# HOMADOS_v1.net
KiCad netlist of a schematic drawn in EAGLE
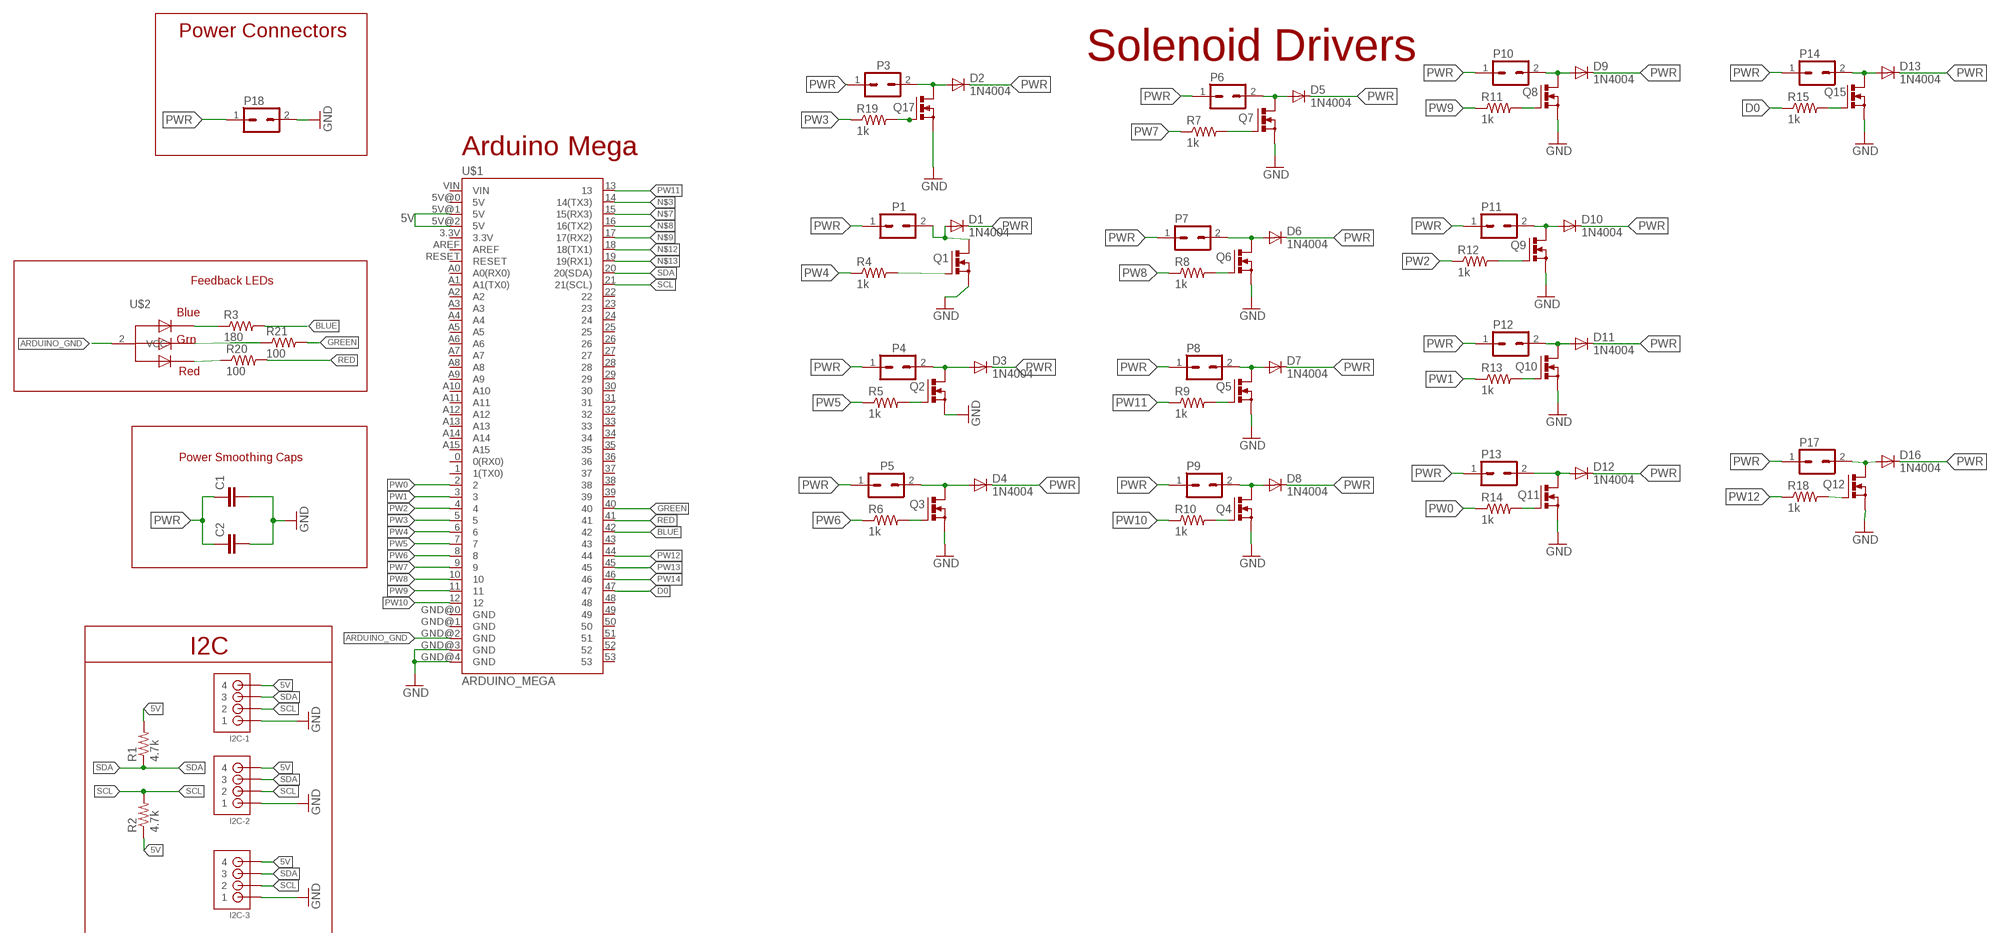
[diagram p0: schematic, sheet 1]

(export (version "E")
  (design (tool "Eeschema 10.0.6"))
  (components
    (comp (ref "C1")
      (value "CAPPTH1")
      (footprint "eagle-import:CAP-PTH-5MM")
      (libsource (lib "eagle-import") (part "CAPPTH1"))
    )
    (comp (ref "C2")
      (value "CAPPTH3")
      (footprint "eagle-import:CAP-PTH-LARGE")
      (libsource (lib "eagle-import") (part "CAPPTH3"))
    )
    (comp (ref "D1")
      (value "1N4004")
      (footprint "eagle-import:DO41-10")
      (libsource (lib "eagle-import") (part "1N4004"))
    )
    (comp (ref "D2")
      (value "1N4004")
      (footprint "eagle-import:DO41-10")
      (libsource (lib "eagle-import") (part "1N4004"))
    )
    (comp (ref "D3")
      (value "1N4004")
      (footprint "eagle-import:DO41-10")
      (libsource (lib "eagle-import") (part "1N4004"))
    )
    (comp (ref "D4")
      (value "1N4004")
      (footprint "eagle-import:DO41-10")
      (libsource (lib "eagle-import") (part "1N4004"))
    )
    (comp (ref "D5")
      (value "1N4004")
      (footprint "eagle-import:DO41-10")
      (libsource (lib "eagle-import") (part "1N4004"))
    )
    (comp (ref "D6")
      (value "1N4004")
      (footprint "eagle-import:DO41-10")
      (libsource (lib "eagle-import") (part "1N4004"))
    )
    (comp (ref "D7")
      (value "1N4004")
      (footprint "eagle-import:DO41-10")
      (libsource (lib "eagle-import") (part "1N4004"))
    )
    (comp (ref "D8")
      (value "1N4004")
      (footprint "eagle-import:DO41-10")
      (libsource (lib "eagle-import") (part "1N4004"))
    )
    (comp (ref "D9")
      (value "1N4004")
      (footprint "eagle-import:DO41-10")
      (libsource (lib "eagle-import") (part "1N4004"))
    )
    (comp (ref "D10")
      (value "1N4004")
      (footprint "eagle-import:DO41-10")
      (libsource (lib "eagle-import") (part "1N4004"))
    )
    (comp (ref "D11")
      (value "1N4004")
      (footprint "eagle-import:DO41-10")
      (libsource (lib "eagle-import") (part "1N4004"))
    )
    (comp (ref "D12")
      (value "1N4004")
      (footprint "eagle-import:DO41-10")
      (libsource (lib "eagle-import") (part "1N4004"))
    )
    (comp (ref "D13")
      (value "1N4004")
      (footprint "eagle-import:DO41-10")
      (libsource (lib "eagle-import") (part "1N4004"))
    )
    (comp (ref "D16")
      (value "1N4004")
      (footprint "eagle-import:DO41-10")
      (libsource (lib "eagle-import") (part "1N4004"))
    )
    (comp (ref "I2C-1")
      (value "JST-PH_4-PIN_HEADER")
      (footprint "eagle-import:JST_B4B-PH_HEADER")
      (libsource (lib "eagle-import") (part "JST-PH_4-PIN_HEADER"))
    )
    (comp (ref "I2C-2")
      (value "JST-PH_4-PIN_HEADER")
      (footprint "eagle-import:JST_B4B-PH_HEADER")
      (libsource (lib "eagle-import") (part "JST-PH_4-PIN_HEADER"))
    )
    (comp (ref "I2C-3")
      (value "JST-PH_4-PIN_HEADER")
      (footprint "eagle-import:JST_B4B-PH_HEADER")
      (libsource (lib "eagle-import") (part "JST-PH_4-PIN_HEADER"))
    )
    (comp (ref "P1")
      (value "39-30-02")
      (footprint "eagle-import:39-30-_02_")
      (libsource (lib "eagle-import") (part "39-30-?02?"))
    )
    (comp (ref "P3")
      (value "39-30-02")
      (footprint "eagle-import:39-30-_02_")
      (libsource (lib "eagle-import") (part "39-30-?02?"))
    )
    (comp (ref "P4")
      (value "39-30-02")
      (footprint "eagle-import:39-30-_02_")
      (libsource (lib "eagle-import") (part "39-30-?02?"))
    )
    (comp (ref "P5")
      (value "39-30-02")
      (footprint "eagle-import:39-30-_02_")
      (libsource (lib "eagle-import") (part "39-30-?02?"))
    )
    (comp (ref "P6")
      (value "39-30-02")
      (footprint "eagle-import:39-30-_02_")
      (libsource (lib "eagle-import") (part "39-30-?02?"))
    )
    (comp (ref "P7")
      (value "39-30-02")
      (footprint "eagle-import:39-30-_02_")
      (libsource (lib "eagle-import") (part "39-30-?02?"))
    )
    (comp (ref "P8")
      (value "39-30-02")
      (footprint "eagle-import:39-30-_02_")
      (libsource (lib "eagle-import") (part "39-30-?02?"))
    )
    (comp (ref "P9")
      (value "39-30-02")
      (footprint "eagle-import:39-30-_02_")
      (libsource (lib "eagle-import") (part "39-30-?02?"))
    )
    (comp (ref "P10")
      (value "39-30-02")
      (footprint "eagle-import:39-30-_02_")
      (libsource (lib "eagle-import") (part "39-30-?02?"))
    )
    (comp (ref "P11")
      (value "39-30-02")
      (footprint "eagle-import:39-30-_02_")
      (libsource (lib "eagle-import") (part "39-30-?02?"))
    )
    (comp (ref "P12")
      (value "39-30-02")
      (footprint "eagle-import:39-30-_02_")
      (libsource (lib "eagle-import") (part "39-30-?02?"))
    )
    (comp (ref "P13")
      (value "39-30-02")
      (footprint "eagle-import:39-30-_02_")
      (libsource (lib "eagle-import") (part "39-30-?02?"))
    )
    (comp (ref "P14")
      (value "39-30-02")
      (footprint "eagle-import:39-30-_02_")
      (libsource (lib "eagle-import") (part "39-30-?02?"))
    )
    (comp (ref "P17")
      (value "39-30-02")
      (footprint "eagle-import:39-30-_02_")
      (libsource (lib "eagle-import") (part "39-30-?02?"))
    )
    (comp (ref "P18")
      (value "39-30-02")
      (footprint "eagle-import:39-30-_02_")
      (libsource (lib "eagle-import") (part "39-30-?02?"))
    )
    (comp (ref "Q1")
      (value "PMOSFET_NTO220BV")
      (footprint "eagle-import:TO220BV")
      (libsource (lib "eagle-import") (part "PMOSFET_NTO220BV"))
    )
    (comp (ref "Q2")
      (value "PMOSFET_NTO220BV")
      (footprint "eagle-import:TO220BV")
      (libsource (lib "eagle-import") (part "PMOSFET_NTO220BV"))
    )
    (comp (ref "Q3")
      (value "PMOSFET_NTO220BV")
      (footprint "eagle-import:TO220BV")
      (libsource (lib "eagle-import") (part "PMOSFET_NTO220BV"))
    )
    (comp (ref "Q4")
      (value "PMOSFET_NTO220BV")
      (footprint "eagle-import:TO220BV")
      (libsource (lib "eagle-import") (part "PMOSFET_NTO220BV"))
    )
    (comp (ref "Q5")
      (value "PMOSFET_NTO220BV")
      (footprint "eagle-import:TO220BV")
      (libsource (lib "eagle-import") (part "PMOSFET_NTO220BV"))
    )
    (comp (ref "Q6")
      (value "PMOSFET_NTO220BV")
      (footprint "eagle-import:TO220BV")
      (libsource (lib "eagle-import") (part "PMOSFET_NTO220BV"))
    )
    (comp (ref "Q7")
      (value "PMOSFET_NTO220BV")
      (footprint "eagle-import:TO220BV")
      (libsource (lib "eagle-import") (part "PMOSFET_NTO220BV"))
    )
    (comp (ref "Q8")
      (value "PMOSFET_NTO220BV")
      (footprint "eagle-import:TO220BV")
      (libsource (lib "eagle-import") (part "PMOSFET_NTO220BV"))
    )
    (comp (ref "Q9")
      (value "PMOSFET_NTO220BV")
      (footprint "eagle-import:TO220BV")
      (libsource (lib "eagle-import") (part "PMOSFET_NTO220BV"))
    )
    (comp (ref "Q10")
      (value "PMOSFET_NTO220BV")
      (footprint "eagle-import:TO220BV")
      (libsource (lib "eagle-import") (part "PMOSFET_NTO220BV"))
    )
    (comp (ref "Q11")
      (value "PMOSFET_NTO220BV")
      (footprint "eagle-import:TO220BV")
      (libsource (lib "eagle-import") (part "PMOSFET_NTO220BV"))
    )
    (comp (ref "Q12")
      (value "PMOSFET_NTO220BV")
      (footprint "eagle-import:TO220BV")
      (libsource (lib "eagle-import") (part "PMOSFET_NTO220BV"))
    )
    (comp (ref "Q15")
      (value "PMOSFET_NTO220BV")
      (footprint "eagle-import:TO220BV")
      (libsource (lib "eagle-import") (part "PMOSFET_NTO220BV"))
    )
    (comp (ref "Q17")
      (value "PMOSFET_NTO220BV")
      (footprint "eagle-import:TO220BV")
      (libsource (lib "eagle-import") (part "PMOSFET_NTO220BV"))
    )
    (comp (ref "R1")
      (value "4.7k")
      (footprint "eagle-import:AXIAL-0.3-KIT")
      (libsource (lib "eagle-import") (part "RESISTORKIT"))
    )
    (comp (ref "R2")
      (value "4.7k")
      (footprint "eagle-import:AXIAL-0.3-KIT")
      (libsource (lib "eagle-import") (part "RESISTORKIT"))
    )
    (comp (ref "R3")
      (value "180")
      (footprint "eagle-import:AXIAL-0.3-KIT")
      (libsource (lib "eagle-import") (part "RESISTORKIT"))
    )
    (comp (ref "R4")
      (value "1k")
      (footprint "eagle-import:AXIAL-0.3-KIT")
      (libsource (lib "eagle-import") (part "RESISTORKIT"))
    )
    (comp (ref "R5")
      (value "1k")
      (footprint "eagle-import:AXIAL-0.3-KIT")
      (libsource (lib "eagle-import") (part "RESISTORKIT"))
    )
    (comp (ref "R6")
      (value "1k")
      (footprint "eagle-import:AXIAL-0.3-KIT")
      (libsource (lib "eagle-import") (part "RESISTORKIT"))
    )
    (comp (ref "R7")
      (value "1k")
      (footprint "eagle-import:AXIAL-0.3-KIT")
      (libsource (lib "eagle-import") (part "RESISTORKIT"))
    )
    (comp (ref "R8")
      (value "1k")
      (footprint "eagle-import:AXIAL-0.3-KIT")
      (libsource (lib "eagle-import") (part "RESISTORKIT"))
    )
    (comp (ref "R9")
      (value "1k")
      (footprint "eagle-import:AXIAL-0.3-KIT")
      (libsource (lib "eagle-import") (part "RESISTORKIT"))
    )
    (comp (ref "R10")
      (value "1k")
      (footprint "eagle-import:AXIAL-0.3-KIT")
      (libsource (lib "eagle-import") (part "RESISTORKIT"))
    )
    (comp (ref "R11")
      (value "1k")
      (footprint "eagle-import:AXIAL-0.3-KIT")
      (libsource (lib "eagle-import") (part "RESISTORKIT"))
    )
    (comp (ref "R12")
      (value "1k")
      (footprint "eagle-import:AXIAL-0.3-KIT")
      (libsource (lib "eagle-import") (part "RESISTORKIT"))
    )
    (comp (ref "R13")
      (value "1k")
      (footprint "eagle-import:AXIAL-0.3-KIT")
      (libsource (lib "eagle-import") (part "RESISTORKIT"))
    )
    (comp (ref "R14")
      (value "1k")
      (footprint "eagle-import:AXIAL-0.3-KIT")
      (libsource (lib "eagle-import") (part "RESISTORKIT"))
    )
    (comp (ref "R15")
      (value "1k")
      (footprint "eagle-import:AXIAL-0.3-KIT")
      (libsource (lib "eagle-import") (part "RESISTORKIT"))
    )
    (comp (ref "R18")
      (value "1k")
      (footprint "eagle-import:AXIAL-0.3-KIT")
      (libsource (lib "eagle-import") (part "RESISTORKIT"))
    )
    (comp (ref "R19")
      (value "1k")
      (footprint "eagle-import:AXIAL-0.3-KIT")
      (libsource (lib "eagle-import") (part "RESISTORKIT"))
    )
    (comp (ref "R20")
      (value "100")
      (footprint "eagle-import:AXIAL-0.3-KIT")
      (libsource (lib "eagle-import") (part "RESISTORKIT"))
    )
    (comp (ref "R21")
      (value "100")
      (footprint "eagle-import:AXIAL-0.3-KIT")
      (libsource (lib "eagle-import") (part "RESISTORKIT"))
    )
    (comp (ref "U$1")
      (value "ARDUINO_MEGA")
      (footprint "eagle-import:ARDUINO_MEGA")
      (libsource (lib "eagle-import") (part "ARDUINO_MEGA"))
    )
    (comp (ref "U$2")
      (value "RGBLED_CA")
      (footprint "eagle-import:LED5MMRGB")
      (libsource (lib "eagle-import") (part "RGBLED_CA"))
    )
  )
  (nets
    (net (code "1") (name "5V") (class "Default")
      (node (ref "I2C-1") (pin "P4") (pinfunction "4_P4") (pintype "bidirectional"))
      (node (ref "I2C-2") (pin "P4") (pinfunction "4_P4") (pintype "bidirectional"))
      (node (ref "I2C-3") (pin "P4") (pinfunction "4_P4") (pintype "bidirectional"))
      (node (ref "R1") (pin "P$2") (pinfunction "2_P$2") (pintype "passive"))
      (node (ref "R2") (pin "P$1") (pinfunction "1_P$1") (pintype "passive"))
      (node (ref "U$1") (pin "5V@1") (pinfunction "5V_5V@1") (pintype "bidirectional"))
      (node (ref "U$1") (pin "5V@2") (pinfunction "5V_5V@2") (pintype "bidirectional"))
    )
    (net (code "2") (name "ARDUINO_GND") (class "Default")
      (node (ref "U$1") (pin "GND@2") (pinfunction "GND_GND@2") (pintype "bidirectional"))
      (node (ref "U$2") (pin "2") (pinfunction "VCC_2") (pintype "bidirectional"))
    )
    (net (code "3") (name "BLUE") (class "Default")
      (node (ref "R3") (pin "P$2") (pinfunction "2_P$2") (pintype "passive"))
      (node (ref "U$1") (pin "42") (pinfunction "42_42") (pintype "bidirectional"))
    )
    (net (code "4") (name "D0") (class "Default")
      (node (ref "R15") (pin "P$1") (pinfunction "1_P$1") (pintype "passive"))
      (node (ref "U$1") (pin "47") (pinfunction "47_47") (pintype "bidirectional"))
    )
    (net (code "5") (name "GND") (class "Default")
      (node (ref "C1") (pin "2") (pinfunction "2_2") (pintype "passive"))
      (node (ref "C2") (pin "2") (pinfunction "2_2") (pintype "passive"))
      (node (ref "I2C-1") (pin "P1") (pinfunction "1_P1") (pintype "bidirectional"))
      (node (ref "I2C-2") (pin "P1") (pinfunction "1_P1") (pintype "bidirectional"))
      (node (ref "I2C-3") (pin "P1") (pinfunction "1_P1") (pintype "bidirectional"))
      (node (ref "P18") (pin "2") (pinfunction "2_2") (pintype "passive"))
      (node (ref "Q1") (pin "S") (pinfunction "S_S") (pintype "passive"))
      (node (ref "Q10") (pin "S") (pinfunction "S_S") (pintype "passive"))
      (node (ref "Q11") (pin "S") (pinfunction "S_S") (pintype "passive"))
      (node (ref "Q12") (pin "S") (pinfunction "S_S") (pintype "passive"))
      (node (ref "Q15") (pin "S") (pinfunction "S_S") (pintype "passive"))
      (node (ref "Q17") (pin "S") (pinfunction "S_S") (pintype "passive"))
      (node (ref "Q2") (pin "S") (pinfunction "S_S") (pintype "passive"))
      (node (ref "Q3") (pin "S") (pinfunction "S_S") (pintype "passive"))
      (node (ref "Q4") (pin "S") (pinfunction "S_S") (pintype "passive"))
      (node (ref "Q5") (pin "S") (pinfunction "S_S") (pintype "passive"))
      (node (ref "Q6") (pin "S") (pinfunction "S_S") (pintype "passive"))
      (node (ref "Q7") (pin "S") (pinfunction "S_S") (pintype "passive"))
      (node (ref "Q8") (pin "S") (pinfunction "S_S") (pintype "passive"))
      (node (ref "Q9") (pin "S") (pinfunction "S_S") (pintype "passive"))
      (node (ref "U$1") (pin "GND@3") (pinfunction "GND_GND@3") (pintype "bidirectional"))
      (node (ref "U$1") (pin "GND@4") (pinfunction "GND_GND@4") (pintype "bidirectional"))
    )
    (net (code "6") (name "GREEN") (class "Default")
      (node (ref "R21") (pin "P$2") (pinfunction "2_P$2") (pintype "passive"))
      (node (ref "U$1") (pin "40") (pinfunction "40_40") (pintype "bidirectional"))
    )
    (net (code "7") (name "N$3") (class "Default")
      (node (ref "U$1") (pin "14") (pinfunction "14(TX3)_14") (pintype "bidirectional"))
    )
    (net (code "8") (name "N$7") (class "Default")
      (node (ref "U$1") (pin "15") (pinfunction "15(RX3)_15") (pintype "bidirectional"))
    )
    (net (code "9") (name "N$8") (class "Default")
      (node (ref "U$1") (pin "16") (pinfunction "16(TX2)_16") (pintype "bidirectional"))
    )
    (net (code "10") (name "N$9") (class "Default")
      (node (ref "U$1") (pin "17") (pinfunction "17(RX2)_17") (pintype "bidirectional"))
    )
    (net (code "11") (name "N$12") (class "Default")
      (node (ref "U$1") (pin "18") (pinfunction "18(TX1)_18") (pintype "bidirectional"))
    )
    (net (code "12") (name "N$13") (class "Default")
      (node (ref "U$1") (pin "19") (pinfunction "19(RX1)_19") (pintype "bidirectional"))
    )
    (net (code "13") (name "Net-(D1-PadA)") (class "Default")
      (node (ref "D1") (pin "A") (pinfunction "A_A") (pintype "passive"))
      (node (ref "P1") (pin "2") (pinfunction "2_2") (pintype "passive"))
      (node (ref "Q1") (pin "D") (pinfunction "D_D") (pintype "passive"))
    )
    (net (code "14") (name "Net-(D2-PadA)") (class "Default")
      (node (ref "D2") (pin "A") (pinfunction "A_A") (pintype "passive"))
      (node (ref "P3") (pin "2") (pinfunction "2_2") (pintype "passive"))
      (node (ref "Q17") (pin "D") (pinfunction "D_D") (pintype "passive"))
    )
    (net (code "15") (name "Net-(D3-PadA)") (class "Default")
      (node (ref "D3") (pin "A") (pinfunction "A_A") (pintype "passive"))
      (node (ref "P4") (pin "2") (pinfunction "2_2") (pintype "passive"))
      (node (ref "Q2") (pin "D") (pinfunction "D_D") (pintype "passive"))
    )
    (net (code "16") (name "Net-(D4-PadA)") (class "Default")
      (node (ref "D4") (pin "A") (pinfunction "A_A") (pintype "passive"))
      (node (ref "P5") (pin "2") (pinfunction "2_2") (pintype "passive"))
      (node (ref "Q3") (pin "D") (pinfunction "D_D") (pintype "passive"))
    )
    (net (code "17") (name "Net-(D5-PadA)") (class "Default")
      (node (ref "D5") (pin "A") (pinfunction "A_A") (pintype "passive"))
      (node (ref "P6") (pin "2") (pinfunction "2_2") (pintype "passive"))
      (node (ref "Q7") (pin "D") (pinfunction "D_D") (pintype "passive"))
    )
    (net (code "18") (name "Net-(D6-PadA)") (class "Default")
      (node (ref "D6") (pin "A") (pinfunction "A_A") (pintype "passive"))
      (node (ref "P7") (pin "2") (pinfunction "2_2") (pintype "passive"))
      (node (ref "Q6") (pin "D") (pinfunction "D_D") (pintype "passive"))
    )
    (net (code "19") (name "Net-(D7-PadA)") (class "Default")
      (node (ref "D7") (pin "A") (pinfunction "A_A") (pintype "passive"))
      (node (ref "P8") (pin "2") (pinfunction "2_2") (pintype "passive"))
      (node (ref "Q5") (pin "D") (pinfunction "D_D") (pintype "passive"))
    )
    (net (code "20") (name "Net-(D8-PadA)") (class "Default")
      (node (ref "D8") (pin "A") (pinfunction "A_A") (pintype "passive"))
      (node (ref "P9") (pin "2") (pinfunction "2_2") (pintype "passive"))
      (node (ref "Q4") (pin "D") (pinfunction "D_D") (pintype "passive"))
    )
    (net (code "21") (name "Net-(D9-PadA)") (class "Default")
      (node (ref "D9") (pin "A") (pinfunction "A_A") (pintype "passive"))
      (node (ref "P10") (pin "2") (pinfunction "2_2") (pintype "passive"))
      (node (ref "Q8") (pin "D") (pinfunction "D_D") (pintype "passive"))
    )
    (net (code "22") (name "Net-(D10-PadA)") (class "Default")
      (node (ref "D10") (pin "A") (pinfunction "A_A") (pintype "passive"))
      (node (ref "P11") (pin "2") (pinfunction "2_2") (pintype "passive"))
      (node (ref "Q9") (pin "D") (pinfunction "D_D") (pintype "passive"))
    )
    (net (code "23") (name "Net-(D11-PadA)") (class "Default")
      (node (ref "D11") (pin "A") (pinfunction "A_A") (pintype "passive"))
      (node (ref "P12") (pin "2") (pinfunction "2_2") (pintype "passive"))
      (node (ref "Q10") (pin "D") (pinfunction "D_D") (pintype "passive"))
    )
    (net (code "24") (name "Net-(D12-PadA)") (class "Default")
      (node (ref "D12") (pin "A") (pinfunction "A_A") (pintype "passive"))
      (node (ref "P13") (pin "2") (pinfunction "2_2") (pintype "passive"))
      (node (ref "Q11") (pin "D") (pinfunction "D_D") (pintype "passive"))
    )
    (net (code "25") (name "Net-(D13-PadA)") (class "Default")
      (node (ref "D13") (pin "A") (pinfunction "A_A") (pintype "passive"))
      (node (ref "P14") (pin "2") (pinfunction "2_2") (pintype "passive"))
      (node (ref "Q15") (pin "D") (pinfunction "D_D") (pintype "passive"))
    )
    (net (code "26") (name "Net-(D16-PadA)") (class "Default")
      (node (ref "D16") (pin "A") (pinfunction "A_A") (pintype "passive"))
      (node (ref "P17") (pin "2") (pinfunction "2_2") (pintype "passive"))
      (node (ref "Q12") (pin "D") (pinfunction "D_D") (pintype "passive"))
    )
    (net (code "27") (name "Net-(R3-1)") (class "Default")
      (node (ref "R3") (pin "P$1") (pinfunction "1_P$1") (pintype "passive"))
      (node (ref "U$2") (pin "4") (pinfunction "BLUE_4") (pintype "bidirectional"))
    )
    (net (code "28") (name "Net-(R4-2)") (class "Default")
      (node (ref "Q1") (pin "G") (pinfunction "G_G") (pintype "passive"))
      (node (ref "R4") (pin "P$2") (pinfunction "2_P$2") (pintype "passive"))
    )
    (net (code "29") (name "Net-(R5-2)") (class "Default")
      (node (ref "Q2") (pin "G") (pinfunction "G_G") (pintype "passive"))
      (node (ref "R5") (pin "P$2") (pinfunction "2_P$2") (pintype "passive"))
    )
    (net (code "30") (name "Net-(R6-2)") (class "Default")
      (node (ref "Q3") (pin "G") (pinfunction "G_G") (pintype "passive"))
      (node (ref "R6") (pin "P$2") (pinfunction "2_P$2") (pintype "passive"))
    )
    (net (code "31") (name "Net-(R7-2)") (class "Default")
      (node (ref "Q7") (pin "G") (pinfunction "G_G") (pintype "passive"))
      (node (ref "R7") (pin "P$2") (pinfunction "2_P$2") (pintype "passive"))
    )
    (net (code "32") (name "Net-(R8-2)") (class "Default")
      (node (ref "Q6") (pin "G") (pinfunction "G_G") (pintype "passive"))
      (node (ref "R8") (pin "P$2") (pinfunction "2_P$2") (pintype "passive"))
    )
    (net (code "33") (name "Net-(R9-2)") (class "Default")
      (node (ref "Q5") (pin "G") (pinfunction "G_G") (pintype "passive"))
      (node (ref "R9") (pin "P$2") (pinfunction "2_P$2") (pintype "passive"))
    )
    (net (code "34") (name "Net-(R10-2)") (class "Default")
      (node (ref "Q4") (pin "G") (pinfunction "G_G") (pintype "passive"))
      (node (ref "R10") (pin "P$2") (pinfunction "2_P$2") (pintype "passive"))
    )
    (net (code "35") (name "Net-(R11-2)") (class "Default")
      (node (ref "Q8") (pin "G") (pinfunction "G_G") (pintype "passive"))
      (node (ref "R11") (pin "P$2") (pinfunction "2_P$2") (pintype "passive"))
    )
    (net (code "36") (name "Net-(R12-2)") (class "Default")
      (node (ref "Q9") (pin "G") (pinfunction "G_G") (pintype "passive"))
      (node (ref "R12") (pin "P$2") (pinfunction "2_P$2") (pintype "passive"))
    )
    (net (code "37") (name "Net-(R13-2)") (class "Default")
      (node (ref "Q10") (pin "G") (pinfunction "G_G") (pintype "passive"))
      (node (ref "R13") (pin "P$2") (pinfunction "2_P$2") (pintype "passive"))
    )
    (net (code "38") (name "Net-(R14-2)") (class "Default")
      (node (ref "Q11") (pin "G") (pinfunction "G_G") (pintype "passive"))
      (node (ref "R14") (pin "P$2") (pinfunction "2_P$2") (pintype "passive"))
    )
    (net (code "39") (name "Net-(R15-2)") (class "Default")
      (node (ref "Q15") (pin "G") (pinfunction "G_G") (pintype "passive"))
      (node (ref "R15") (pin "P$2") (pinfunction "2_P$2") (pintype "passive"))
    )
    (net (code "40") (name "Net-(R18-2)") (class "Default")
      (node (ref "Q12") (pin "G") (pinfunction "G_G") (pintype "passive"))
      (node (ref "R18") (pin "P$2") (pinfunction "2_P$2") (pintype "passive"))
    )
    (net (code "41") (name "Net-(R19-2)") (class "Default")
      (node (ref "Q17") (pin "G") (pinfunction "G_G") (pintype "passive"))
      (node (ref "R19") (pin "P$2") (pinfunction "2_P$2") (pintype "passive"))
    )
    (net (code "42") (name "Net-(R20-1)") (class "Default")
      (node (ref "R20") (pin "P$1") (pinfunction "1_P$1") (pintype "passive"))
      (node (ref "U$2") (pin "1") (pinfunction "RED_1") (pintype "bidirectional"))
    )
    (net (code "43") (name "Net-(R21-1)") (class "Default")
      (node (ref "R21") (pin "P$1") (pinfunction "1_P$1") (pintype "passive"))
      (node (ref "U$2") (pin "3") (pinfunction "GREEN_3") (pintype "bidirectional"))
    )
    (net (code "44") (name "PW0") (class "Default")
      (node (ref "R14") (pin "P$1") (pinfunction "1_P$1") (pintype "passive"))
      (node (ref "U$1") (pin "2") (pinfunction "2_2") (pintype "bidirectional"))
    )
    (net (code "45") (name "PW1") (class "Default")
      (node (ref "R13") (pin "P$1") (pinfunction "1_P$1") (pintype "passive"))
      (node (ref "U$1") (pin "3") (pinfunction "3_3") (pintype "bidirectional"))
    )
    (net (code "46") (name "PW2") (class "Default")
      (node (ref "R12") (pin "P$1") (pinfunction "1_P$1") (pintype "passive"))
      (node (ref "U$1") (pin "4") (pinfunction "4_4") (pintype "bidirectional"))
    )
    (net (code "47") (name "PW3") (class "Default")
      (node (ref "R19") (pin "P$1") (pinfunction "1_P$1") (pintype "passive"))
      (node (ref "U$1") (pin "5") (pinfunction "5_5") (pintype "bidirectional"))
    )
    (net (code "48") (name "PW4") (class "Default")
      (node (ref "R4") (pin "P$1") (pinfunction "1_P$1") (pintype "passive"))
      (node (ref "U$1") (pin "6") (pinfunction "6_6") (pintype "bidirectional"))
    )
    (net (code "49") (name "PW5") (class "Default")
      (node (ref "R5") (pin "P$1") (pinfunction "1_P$1") (pintype "passive"))
      (node (ref "U$1") (pin "7") (pinfunction "7_7") (pintype "bidirectional"))
    )
    (net (code "50") (name "PW6") (class "Default")
      (node (ref "R6") (pin "P$1") (pinfunction "1_P$1") (pintype "passive"))
      (node (ref "U$1") (pin "8") (pinfunction "8_8") (pintype "bidirectional"))
    )
    (net (code "51") (name "PW7") (class "Default")
      (node (ref "R7") (pin "P$1") (pinfunction "1_P$1") (pintype "passive"))
      (node (ref "U$1") (pin "9") (pinfunction "9_9") (pintype "bidirectional"))
    )
    (net (code "52") (name "PW8") (class "Default")
      (node (ref "R8") (pin "P$1") (pinfunction "1_P$1") (pintype "passive"))
      (node (ref "U$1") (pin "10") (pinfunction "10_10") (pintype "bidirectional"))
    )
    (net (code "53") (name "PW9") (class "Default")
      (node (ref "R11") (pin "P$1") (pinfunction "1_P$1") (pintype "passive"))
      (node (ref "U$1") (pin "11") (pinfunction "11_11") (pintype "bidirectional"))
    )
    (net (code "54") (name "PW10") (class "Default")
      (node (ref "R10") (pin "P$1") (pinfunction "1_P$1") (pintype "passive"))
      (node (ref "U$1") (pin "12") (pinfunction "12_12") (pintype "bidirectional"))
    )
    (net (code "55") (name "PW11") (class "Default")
      (node (ref "R9") (pin "P$1") (pinfunction "1_P$1") (pintype "passive"))
      (node (ref "U$1") (pin "13") (pinfunction "13_13") (pintype "bidirectional"))
    )
    (net (code "56") (name "PW12") (class "Default")
      (node (ref "R18") (pin "P$1") (pinfunction "1_P$1") (pintype "passive"))
      (node (ref "U$1") (pin "44") (pinfunction "44_44") (pintype "bidirectional"))
    )
    (net (code "57") (name "PW13") (class "Default")
      (node (ref "U$1") (pin "45") (pinfunction "45_45") (pintype "bidirectional"))
    )
    (net (code "58") (name "PW14") (class "Default")
      (node (ref "U$1") (pin "46") (pinfunction "46_46") (pintype "bidirectional"))
    )
    (net (code "59") (name "PWR") (class "Default")
      (node (ref "C1") (pin "1") (pinfunction "1_1") (pintype "passive"))
      (node (ref "C2") (pin "1") (pinfunction "1_1") (pintype "passive"))
      (node (ref "D1") (pin "C") (pinfunction "C_C") (pintype "passive"))
      (node (ref "D10") (pin "C") (pinfunction "C_C") (pintype "passive"))
      (node (ref "D11") (pin "C") (pinfunction "C_C") (pintype "passive"))
      (node (ref "D12") (pin "C") (pinfunction "C_C") (pintype "passive"))
      (node (ref "D13") (pin "C") (pinfunction "C_C") (pintype "passive"))
      (node (ref "D16") (pin "C") (pinfunction "C_C") (pintype "passive"))
      (node (ref "D2") (pin "C") (pinfunction "C_C") (pintype "passive"))
      (node (ref "D3") (pin "C") (pinfunction "C_C") (pintype "passive"))
      (node (ref "D4") (pin "C") (pinfunction "C_C") (pintype "passive"))
      (node (ref "D5") (pin "C") (pinfunction "C_C") (pintype "passive"))
      (node (ref "D6") (pin "C") (pinfunction "C_C") (pintype "passive"))
      (node (ref "D7") (pin "C") (pinfunction "C_C") (pintype "passive"))
      (node (ref "D8") (pin "C") (pinfunction "C_C") (pintype "passive"))
      (node (ref "D9") (pin "C") (pinfunction "C_C") (pintype "passive"))
      (node (ref "P1") (pin "1") (pinfunction "1_1") (pintype "passive"))
      (node (ref "P10") (pin "1") (pinfunction "1_1") (pintype "passive"))
      (node (ref "P11") (pin "1") (pinfunction "1_1") (pintype "passive"))
      (node (ref "P12") (pin "1") (pinfunction "1_1") (pintype "passive"))
      (node (ref "P13") (pin "1") (pinfunction "1_1") (pintype "passive"))
      (node (ref "P14") (pin "1") (pinfunction "1_1") (pintype "passive"))
      (node (ref "P17") (pin "1") (pinfunction "1_1") (pintype "passive"))
      (node (ref "P18") (pin "1") (pinfunction "1_1") (pintype "passive"))
      (node (ref "P3") (pin "1") (pinfunction "1_1") (pintype "passive"))
      (node (ref "P4") (pin "1") (pinfunction "1_1") (pintype "passive"))
      (node (ref "P5") (pin "1") (pinfunction "1_1") (pintype "passive"))
      (node (ref "P6") (pin "1") (pinfunction "1_1") (pintype "passive"))
      (node (ref "P7") (pin "1") (pinfunction "1_1") (pintype "passive"))
      (node (ref "P8") (pin "1") (pinfunction "1_1") (pintype "passive"))
      (node (ref "P9") (pin "1") (pinfunction "1_1") (pintype "passive"))
    )
    (net (code "60") (name "RED") (class "Default")
      (node (ref "R20") (pin "P$2") (pinfunction "2_P$2") (pintype "passive"))
      (node (ref "U$1") (pin "41") (pinfunction "41_41") (pintype "bidirectional"))
    )
    (net (code "61") (name "SCL") (class "Default")
      (node (ref "I2C-1") (pin "P2") (pinfunction "2_P2") (pintype "bidirectional"))
      (node (ref "I2C-2") (pin "P2") (pinfunction "2_P2") (pintype "bidirectional"))
      (node (ref "I2C-3") (pin "P2") (pinfunction "2_P2") (pintype "bidirectional"))
      (node (ref "R2") (pin "P$2") (pinfunction "2_P$2") (pintype "passive"))
      (node (ref "U$1") (pin "21") (pinfunction "21(SCL)_21") (pintype "bidirectional"))
    )
    (net (code "62") (name "SDA") (class "Default")
      (node (ref "I2C-1") (pin "P3") (pinfunction "3_P3") (pintype "bidirectional"))
      (node (ref "I2C-2") (pin "P3") (pinfunction "3_P3") (pintype "bidirectional"))
      (node (ref "I2C-3") (pin "P3") (pinfunction "3_P3") (pintype "bidirectional"))
      (node (ref "R1") (pin "P$1") (pinfunction "1_P$1") (pintype "passive"))
      (node (ref "U$1") (pin "20") (pinfunction "20(SDA)_20") (pintype "bidirectional"))
    )
    (net (code "63") (name "unconnected-(U$1-0(RX0)-Pad0)") (class "Default")
      (node (ref "U$1") (pin "0") (pinfunction "0(RX0)_0") (pintype "bidirectional"))
    )
    (net (code "64") (name "unconnected-(U$1-1(TX0)-Pad1)") (class "Default")
      (node (ref "U$1") (pin "1") (pinfunction "1(TX0)_1") (pintype "bidirectional"))
    )
    (net (code "65") (name "unconnected-(U$1-5V-Pad5V@0)") (class "Default")
      (node (ref "U$1") (pin "5V@0") (pinfunction "5V_5V@0") (pintype "bidirectional"))
    )
    (net (code "66") (name "unconnected-(U$1-A0(RX0)-PadA0)") (class "Default")
      (node (ref "U$1") (pin "A0") (pinfunction "A0(RX0)_A0") (pintype "bidirectional"))
    )
    (net (code "67") (name "unconnected-(U$1-A1(TX0)-PadA1)") (class "Default")
      (node (ref "U$1") (pin "A1") (pinfunction "A1(TX0)_A1") (pintype "bidirectional"))
    )
    (net (code "68") (name "unconnected-(U$1-GND-PadGND@0)") (class "Default")
      (node (ref "U$1") (pin "GND@0") (pinfunction "GND_GND@0") (pintype "bidirectional"))
    )
    (net (code "69") (name "unconnected-(U$1-GND-PadGND@1)") (class "Default")
      (node (ref "U$1") (pin "GND@1") (pinfunction "GND_GND@1") (pintype "bidirectional"))
    )
    (net (code "70") (name "unconnected-(U$1-Pad3.3V)") (class "Default")
      (node (ref "U$1") (pin "3.3V") (pinfunction "3.3V_3.3V") (pintype "bidirectional"))
    )
    (net (code "71") (name "unconnected-(U$1-Pad22)") (class "Default")
      (node (ref "U$1") (pin "22") (pinfunction "22_22") (pintype "bidirectional"))
    )
    (net (code "72") (name "unconnected-(U$1-Pad23)") (class "Default")
      (node (ref "U$1") (pin "23") (pinfunction "23_23") (pintype "bidirectional"))
    )
    (net (code "73") (name "unconnected-(U$1-Pad24)") (class "Default")
      (node (ref "U$1") (pin "24") (pinfunction "24_24") (pintype "bidirectional"))
    )
    (net (code "74") (name "unconnected-(U$1-Pad25)") (class "Default")
      (node (ref "U$1") (pin "25") (pinfunction "25_25") (pintype "bidirectional"))
    )
    (net (code "75") (name "unconnected-(U$1-Pad26)") (class "Default")
      (node (ref "U$1") (pin "26") (pinfunction "26_26") (pintype "bidirectional"))
    )
    (net (code "76") (name "unconnected-(U$1-Pad27)") (class "Default")
      (node (ref "U$1") (pin "27") (pinfunction "27_27") (pintype "bidirectional"))
    )
    (net (code "77") (name "unconnected-(U$1-Pad28)") (class "Default")
      (node (ref "U$1") (pin "28") (pinfunction "28_28") (pintype "bidirectional"))
    )
    (net (code "78") (name "unconnected-(U$1-Pad29)") (class "Default")
      (node (ref "U$1") (pin "29") (pinfunction "29_29") (pintype "bidirectional"))
    )
    (net (code "79") (name "unconnected-(U$1-Pad30)") (class "Default")
      (node (ref "U$1") (pin "30") (pinfunction "30_30") (pintype "bidirectional"))
    )
    (net (code "80") (name "unconnected-(U$1-Pad31)") (class "Default")
      (node (ref "U$1") (pin "31") (pinfunction "31_31") (pintype "bidirectional"))
    )
    (net (code "81") (name "unconnected-(U$1-Pad32)") (class "Default")
      (node (ref "U$1") (pin "32") (pinfunction "32_32") (pintype "bidirectional"))
    )
    (net (code "82") (name "unconnected-(U$1-Pad33)") (class "Default")
      (node (ref "U$1") (pin "33") (pinfunction "33_33") (pintype "bidirectional"))
    )
    (net (code "83") (name "unconnected-(U$1-Pad34)") (class "Default")
      (node (ref "U$1") (pin "34") (pinfunction "34_34") (pintype "bidirectional"))
    )
    (net (code "84") (name "unconnected-(U$1-Pad35)") (class "Default")
      (node (ref "U$1") (pin "35") (pinfunction "35_35") (pintype "bidirectional"))
    )
    (net (code "85") (name "unconnected-(U$1-Pad36)") (class "Default")
      (node (ref "U$1") (pin "36") (pinfunction "36_36") (pintype "bidirectional"))
    )
    (net (code "86") (name "unconnected-(U$1-Pad37)") (class "Default")
      (node (ref "U$1") (pin "37") (pinfunction "37_37") (pintype "bidirectional"))
    )
    (net (code "87") (name "unconnected-(U$1-Pad38)") (class "Default")
      (node (ref "U$1") (pin "38") (pinfunction "38_38") (pintype "bidirectional"))
    )
    (net (code "88") (name "unconnected-(U$1-Pad39)") (class "Default")
      (node (ref "U$1") (pin "39") (pinfunction "39_39") (pintype "bidirectional"))
    )
    (net (code "89") (name "unconnected-(U$1-Pad43)") (class "Default")
      (node (ref "U$1") (pin "43") (pinfunction "43_43") (pintype "bidirectional"))
    )
    (net (code "90") (name "unconnected-(U$1-Pad48)") (class "Default")
      (node (ref "U$1") (pin "48") (pinfunction "48_48") (pintype "bidirectional"))
    )
    (net (code "91") (name "unconnected-(U$1-Pad49)") (class "Default")
      (node (ref "U$1") (pin "49") (pinfunction "49_49") (pintype "bidirectional"))
    )
    (net (code "92") (name "unconnected-(U$1-Pad50)") (class "Default")
      (node (ref "U$1") (pin "50") (pinfunction "50_50") (pintype "bidirectional"))
    )
    (net (code "93") (name "unconnected-(U$1-Pad51)") (class "Default")
      (node (ref "U$1") (pin "51") (pinfunction "51_51") (pintype "bidirectional"))
    )
    (net (code "94") (name "unconnected-(U$1-Pad52)") (class "Default")
      (node (ref "U$1") (pin "52") (pinfunction "52_52") (pintype "bidirectional"))
    )
    (net (code "95") (name "unconnected-(U$1-Pad53)") (class "Default")
      (node (ref "U$1") (pin "53") (pinfunction "53_53") (pintype "bidirectional"))
    )
    (net (code "96") (name "unconnected-(U$1-PadA2)") (class "Default")
      (node (ref "U$1") (pin "A2") (pinfunction "A2_A2") (pintype "bidirectional"))
    )
    (net (code "97") (name "unconnected-(U$1-PadA3)") (class "Default")
      (node (ref "U$1") (pin "A3") (pinfunction "A3_A3") (pintype "bidirectional"))
    )
    (net (code "98") (name "unconnected-(U$1-PadA4)") (class "Default")
      (node (ref "U$1") (pin "A4") (pinfunction "A4_A4") (pintype "bidirectional"))
    )
    (net (code "99") (name "unconnected-(U$1-PadA5)") (class "Default")
      (node (ref "U$1") (pin "A5") (pinfunction "A5_A5") (pintype "bidirectional"))
    )
    (net (code "100") (name "unconnected-(U$1-PadA6)") (class "Default")
      (node (ref "U$1") (pin "A6") (pinfunction "A6_A6") (pintype "bidirectional"))
    )
    (net (code "101") (name "unconnected-(U$1-PadA7)") (class "Default")
      (node (ref "U$1") (pin "A7") (pinfunction "A7_A7") (pintype "bidirectional"))
    )
    (net (code "102") (name "unconnected-(U$1-PadA8)") (class "Default")
      (node (ref "U$1") (pin "A8") (pinfunction "A8_A8") (pintype "bidirectional"))
    )
    (net (code "103") (name "unconnected-(U$1-PadA9)") (class "Default")
      (node (ref "U$1") (pin "A9") (pinfunction "A9_A9") (pintype "bidirectional"))
    )
    (net (code "104") (name "unconnected-(U$1-PadA10)") (class "Default")
      (node (ref "U$1") (pin "A10") (pinfunction "A10_A10") (pintype "bidirectional"))
    )
    (net (code "105") (name "unconnected-(U$1-PadA11)") (class "Default")
      (node (ref "U$1") (pin "A11") (pinfunction "A11_A11") (pintype "bidirectional"))
    )
    (net (code "106") (name "unconnected-(U$1-PadA12)") (class "Default")
      (node (ref "U$1") (pin "A12") (pinfunction "A12_A12") (pintype "bidirectional"))
    )
    (net (code "107") (name "unconnected-(U$1-PadA13)") (class "Default")
      (node (ref "U$1") (pin "A13") (pinfunction "A13_A13") (pintype "bidirectional"))
    )
    (net (code "108") (name "unconnected-(U$1-PadA14)") (class "Default")
      (node (ref "U$1") (pin "A14") (pinfunction "A14_A14") (pintype "bidirectional"))
    )
    (net (code "109") (name "unconnected-(U$1-PadA15)") (class "Default")
      (node (ref "U$1") (pin "A15") (pinfunction "A15_A15") (pintype "bidirectional"))
    )
    (net (code "110") (name "unconnected-(U$1-PadAREF)") (class "Default")
      (node (ref "U$1") (pin "AREF") (pinfunction "AREF_AREF") (pintype "bidirectional"))
    )
    (net (code "111") (name "unconnected-(U$1-PadRESET)") (class "Default")
      (node (ref "U$1") (pin "RESET") (pinfunction "RESET_RESET") (pintype "bidirectional"))
    )
    (net (code "112") (name "unconnected-(U$1-PadVIN)") (class "Default")
      (node (ref "U$1") (pin "VIN") (pinfunction "VIN_VIN") (pintype "bidirectional"))
    )
  )
)
